# PWM_PPM_FMU_REV_1A.net
KiCad netlist of a schematic drawn in Altium Designer
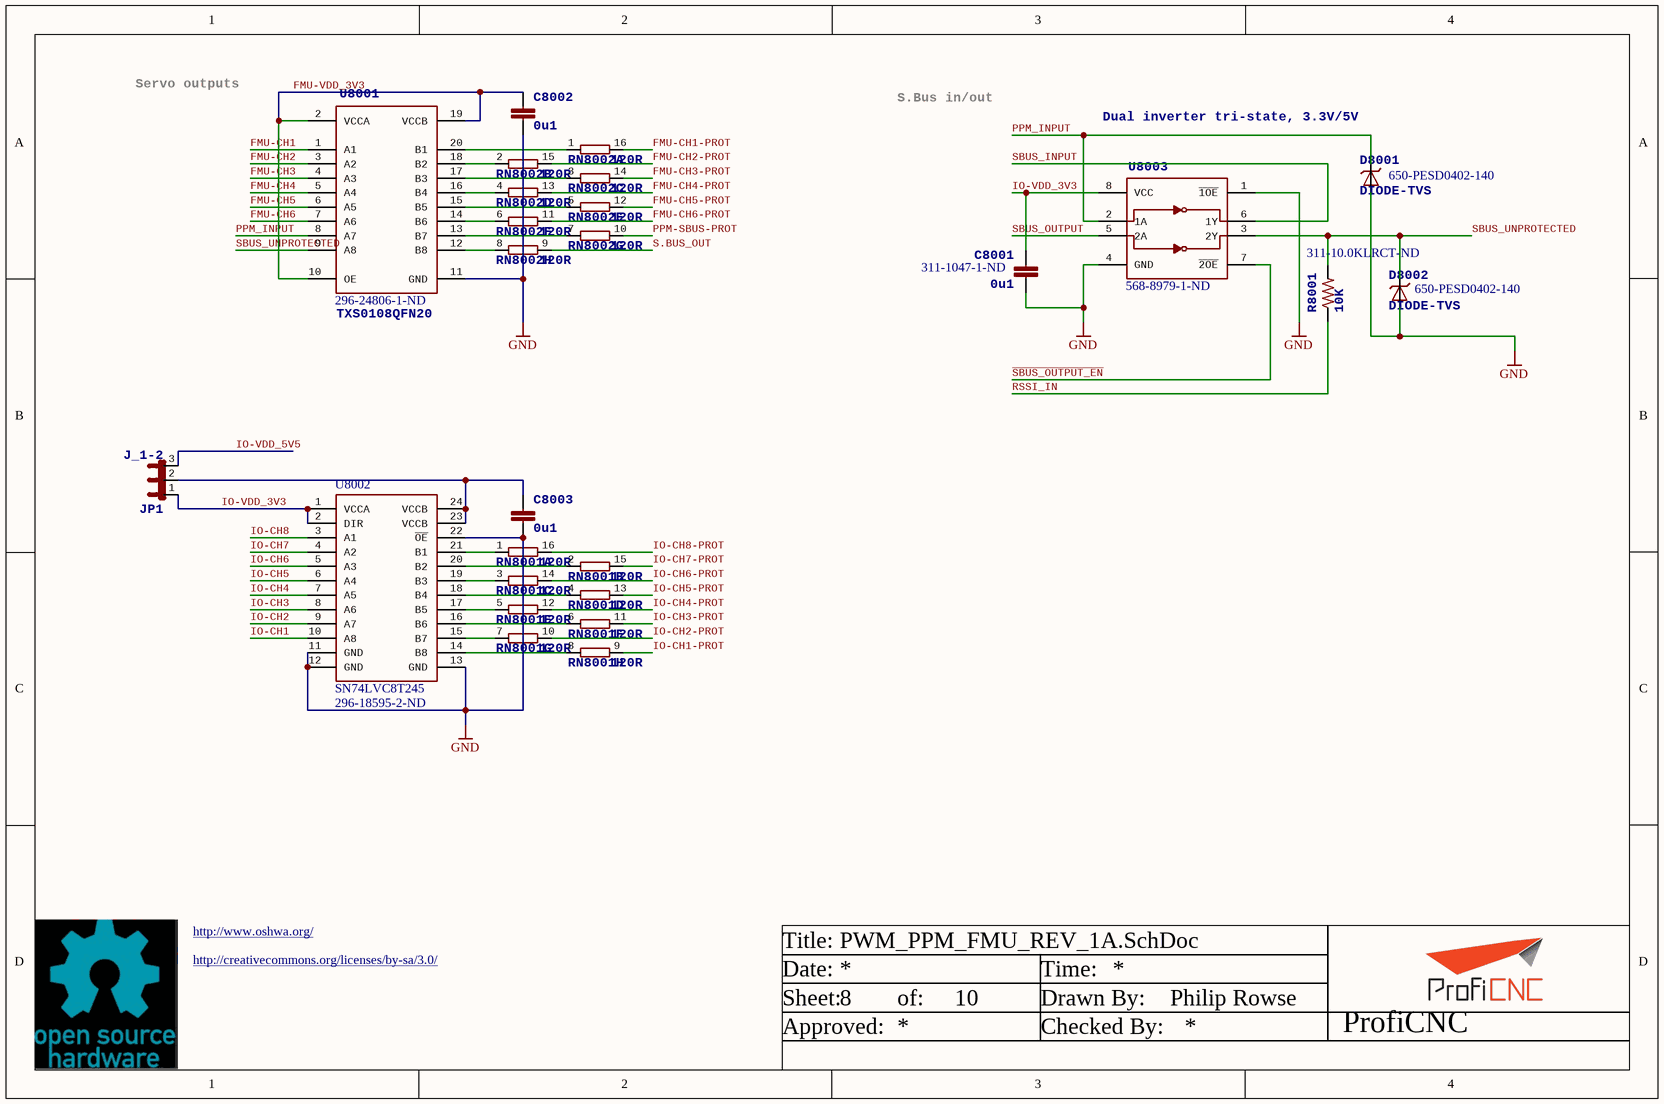
[diagram p0: PWM_PPM_FMU_REV_1A.SchDoc]

(export (version "E")
  (design (tool "Eeschema 10.0.6"))
  (components
    (comp (ref "C8001")
      (value "0u1")
      (footprint "0402-CAP")
      (description "CAP CER 0.1UF 16V Y5V 0402")
      (fields
        (field (name "PARTNO") "CC0402ZRY5V7BB104")
        (field (name "SUPPLIER PART NUMBER 1") "311-1047-1-ND")
        (field (name "3DR_PARTNO") "ECM0700")
      )
      (libsource (lib "") (part "CAP0402_1"))
    )
    (comp (ref "C8002")
      (value "0u1")
      (footprint "0402-CAP")
      (description "CAP CER 0.1UF 16V Y5V 0402")
      (fields (field (name "PARTNO") "CC0402ZRY5V7BB104") (field (name "3DR_PARTNO") "ECM0700"))
      (libsource (lib "pixhawk2") (part "CAP0402"))
    )
    (comp (ref "C8003")
      (value "0u1")
      (footprint "0402-CAP")
      (description "CAP CER 0.1UF 16V Y5V 0402")
      (fields (field (name "PARTNO") "CC0402ZRY5V7BB104") (field (name "3DR_PARTNO") "ECM0700"))
      (libsource (lib "pixhawk2") (part "CAP0402"))
    )
    (comp (ref "D8001")
      (value "DIODE-TVS")
      (footprint "0402-TVS")
      (description "TVS DIODE 14VWM 40VC 0402")
      (fields
        (field (name "SUPPLIER PART NUMBER 1") "650-PESD0402-140")
        (field (name "3DR_PARTNO") "ECM0837")
        (field (name "PARTNO") "PESD0402-140")
      )
      (libsource (lib "pixhawk2") (part "DIODE-TVS"))
    )
    (comp (ref "D8002")
      (value "DIODE-TVS")
      (footprint "0402-TVS")
      (description "TVS DIODE 14VWM 40VC 0402")
      (fields
        (field (name "SUPPLIER PART NUMBER 1") "650-PESD0402-140")
        (field (name "3DR_PARTNO") "ECM0837")
        (field (name "PARTNO") "PESD0402-140")
      )
      (libsource (lib "pixhawk2") (part "DIODE-TVS"))
    )
    (comp (ref "JP1")
      (value "J_1-2")
      (footprint "SJ_3_NO_PLACE_1-2_short")
      (libsource (lib "3DR") (part "JUMPER-31-2"))
    )
    (comp (ref "R8001")
      (value "10K")
      (footprint "0402-RES")
      (description "RES 10K OHM 1/16W 1% 0402 SMD")
      (fields
        (field (name "PARTNO") "RC0402FR-0710KL")
        (field (name "SUPPLIER PART NUMBER 1") "311-10.0KLRCT-ND")
        (field (name "3DR_PARTNO") "ECM0800")
      )
      (libsource (lib "pixhawk2") (part "RESISTOR0402-RES"))
    )
    (comp (ref "RN8001")
      (value "120R")
      (footprint "EXB2HV")
      (description "RES ARRAY 120 OHM 8 RES 1506")
      (fields (field (name "PARTNO") "EXB-2HV121JV") (field (name "3DR_PARTNO") "ECM0266"))
      (libsource (lib "pixhawk2") (part "8R-NEXB2HV-220R"))
    )
    (comp (ref "RN8002")
      (value "120R")
      (footprint "EXB2HV")
      (description "RES ARRAY 120 OHM 8 RES 1506")
      (fields (field (name "PARTNO") "EXB-2HV121JV") (field (name "3DR_PARTNO") "ECM0266"))
      (libsource (lib "pixhawk2") (part "8R-NEXB2HV-220R"))
    )
    (comp (ref "U8001")
      (value "TXS0108QFN20")
      (footprint "QFN20-RGY")
      (description "IC XLATR VOLT-LVL 8B BDIR 20QFN")
      (fields
        (field (name "SUPPLIER PART NUMBER 1") "296-24806-1-ND")
        (field (name "3DR_PARTNO") "ECM0845")
        (field (name "PARTNO") "TXS0108ERGYR")
      )
      (libsource (lib "pixhawk2") (part "TXS0108QFN20"))
    )
    (comp (ref "U8002")
      (value "SN74LVC8T245")
      (footprint "QFN24-RGY")
      (fields (field (name "SUPPLIER PART NUMBER 1") "296-18595-2-ND"))
      (libsource (lib "3DR") (part "SN74LVC8T245"))
    )
    (comp (ref "U8003")
      (value "Dual inverter tri-state, 3.3V/5V")
      (footprint "TSSOP8_SOT505-2")
      (description "IC INVERTER DUAL 4-INPUT 8TSSOP")
      (fields
        (field (name "SUPPLIER PART NUMBER 1") "568-8979-1-ND")
        (field (name "3DR_PARTNO") "ECM0817")
        (field (name "PARTNO") "74LVC2G240DP,125")
      )
      (libsource (lib "pixhawk2") (part "74LVC2G240-TSSOP-8"))
    )
  )
  (nets
    (net (code "1") (name "/FMU-CH1") (class "Default")
      (node (ref "U8001") (pin "1") (pinfunction "A1_1") (pintype "passive"))
    )
    (net (code "2") (name "/FMU-CH1-PROT") (class "Default")
      (node (ref "RN8002") (pin "16") (pinfunction "2_16") (pintype "passive"))
    )
    (net (code "3") (name "/FMU-CH2") (class "Default")
      (node (ref "U8001") (pin "3") (pinfunction "A2_3") (pintype "passive"))
    )
    (net (code "4") (name "/FMU-CH2-PROT") (class "Default")
      (node (ref "RN8002") (pin "15") (pinfunction "2_15") (pintype "passive"))
    )
    (net (code "5") (name "/FMU-CH3") (class "Default")
      (node (ref "U8001") (pin "4") (pinfunction "A3_4") (pintype "passive"))
    )
    (net (code "6") (name "/FMU-CH3-PROT") (class "Default")
      (node (ref "RN8002") (pin "14") (pinfunction "2_14") (pintype "passive"))
    )
    (net (code "7") (name "/FMU-CH4") (class "Default")
      (node (ref "U8001") (pin "5") (pinfunction "A4_5") (pintype "passive"))
    )
    (net (code "8") (name "/FMU-CH4-PROT") (class "Default")
      (node (ref "RN8002") (pin "13") (pinfunction "2_13") (pintype "passive"))
    )
    (net (code "9") (name "/FMU-CH5") (class "Default")
      (node (ref "U8001") (pin "6") (pinfunction "A5_6") (pintype "passive"))
    )
    (net (code "10") (name "/FMU-CH5-PROT") (class "Default")
      (node (ref "RN8002") (pin "12") (pinfunction "2_12") (pintype "passive"))
    )
    (net (code "11") (name "/FMU-CH6") (class "Default")
      (node (ref "U8001") (pin "7") (pinfunction "A6_7") (pintype "passive"))
    )
    (net (code "12") (name "/FMU-CH6-PROT") (class "Default")
      (node (ref "RN8002") (pin "11") (pinfunction "2_11") (pintype "passive"))
    )
    (net (code "13") (name "/FMU-VDD_3V3") (class "Default")
      (node (ref "C8002") (pin "P$1") (pinfunction "1_P$1") (pintype "passive"))
      (node (ref "U8001") (pin "10") (pinfunction "OE_10") (pintype "passive"))
      (node (ref "U8001") (pin "19") (pinfunction "VCCB_19") (pintype "passive"))
      (node (ref "U8001") (pin "2") (pinfunction "VCCA_2") (pintype "passive"))
    )
    (net (code "14") (name "/IO-CH1") (class "Default")
      (node (ref "U8002") (pin "10") (pinfunction "A8_10") (pintype "passive"))
    )
    (net (code "15") (name "/IO-CH1-PROT") (class "Default")
      (node (ref "RN8001") (pin "9") (pinfunction "2_9") (pintype "passive"))
    )
    (net (code "16") (name "/IO-CH2") (class "Default")
      (node (ref "U8002") (pin "9") (pinfunction "A7_9") (pintype "passive"))
    )
    (net (code "17") (name "/IO-CH2-PROT") (class "Default")
      (node (ref "RN8001") (pin "10") (pinfunction "2_10") (pintype "passive"))
    )
    (net (code "18") (name "/IO-CH3") (class "Default")
      (node (ref "U8002") (pin "8") (pinfunction "A6_8") (pintype "passive"))
    )
    (net (code "19") (name "/IO-CH3-PROT") (class "Default")
      (node (ref "RN8001") (pin "11") (pinfunction "2_11") (pintype "passive"))
    )
    (net (code "20") (name "/IO-CH4") (class "Default")
      (node (ref "U8002") (pin "7") (pinfunction "A5_7") (pintype "passive"))
    )
    (net (code "21") (name "/IO-CH4-PROT") (class "Default")
      (node (ref "RN8001") (pin "12") (pinfunction "2_12") (pintype "passive"))
    )
    (net (code "22") (name "/IO-CH5") (class "Default")
      (node (ref "U8002") (pin "6") (pinfunction "A4_6") (pintype "passive"))
    )
    (net (code "23") (name "/IO-CH5-PROT") (class "Default")
      (node (ref "RN8001") (pin "13") (pinfunction "2_13") (pintype "passive"))
    )
    (net (code "24") (name "/IO-CH6") (class "Default")
      (node (ref "U8002") (pin "5") (pinfunction "A3_5") (pintype "passive"))
    )
    (net (code "25") (name "/IO-CH6-PROT") (class "Default")
      (node (ref "RN8001") (pin "14") (pinfunction "2_14") (pintype "passive"))
    )
    (net (code "26") (name "/IO-CH7") (class "Default")
      (node (ref "U8002") (pin "4") (pinfunction "A2_4") (pintype "passive"))
    )
    (net (code "27") (name "/IO-CH7-PROT") (class "Default")
      (node (ref "RN8001") (pin "15") (pinfunction "2_15") (pintype "passive"))
    )
    (net (code "28") (name "/IO-CH8") (class "Default")
      (node (ref "U8002") (pin "3") (pinfunction "A1_3") (pintype "passive"))
    )
    (net (code "29") (name "/IO-CH8-PROT") (class "Default")
      (node (ref "RN8001") (pin "16") (pinfunction "2_16") (pintype "passive"))
    )
    (net (code "30") (name "/IO-VDD_3V3") (class "Default")
      (node (ref "C8001") (pin "P$1") (pinfunction "1_P$1") (pintype "passive"))
      (node (ref "JP1") (pin "1") (pinfunction "1_1") (pintype "passive"))
      (node (ref "U8002") (pin "1") (pinfunction "VCCA_1") (pintype "passive"))
      (node (ref "U8002") (pin "2") (pinfunction "DIR_2") (pintype "passive"))
      (node (ref "U8003") (pin "8") (pinfunction "VCC_8") (pintype "open_emitter"))
    )
    (net (code "31") (name "/IO-VDD_5V5") (class "Default")
      (node (ref "JP1") (pin "3") (pinfunction "3_3") (pintype "passive"))
    )
    (net (code "32") (name "/PPM-SBUS-PROT") (class "Default")
      (node (ref "RN8002") (pin "10") (pinfunction "2_10") (pintype "passive"))
    )
    (net (code "33") (name "/PPM_INPUT") (class "Default")
      (node (ref "D8001") (pin "C") (pinfunction "C_C") (pintype "passive"))
      (node (ref "U8001") (pin "8") (pinfunction "A7_8") (pintype "passive"))
      (node (ref "U8003") (pin "2") (pinfunction "1A_2") (pintype "passive"))
    )
    (net (code "34") (name "/RSSI_IN") (class "Default")
      (node (ref "R8001") (pin "P$1") (pinfunction "1_P$1") (pintype "passive"))
    )
    (net (code "35") (name "/S.BUS_OUT") (class "Default")
      (node (ref "RN8002") (pin "9") (pinfunction "2_9") (pintype "passive"))
    )
    (net (code "36") (name "/SBUS_INPUT") (class "Default")
      (node (ref "U8003") (pin "6") (pinfunction "1Y_6") (pintype "passive"))
    )
    (net (code "37") (name "/SBUS_OUTPUT") (class "Default")
      (node (ref "U8003") (pin "5") (pinfunction "2A_5") (pintype "passive"))
    )
    (net (code "38") (name "/SBUS_UNPROTECTED") (class "Default")
      (node (ref "D8002") (pin "C") (pinfunction "C_C") (pintype "passive"))
      (node (ref "R8001") (pin "P$2") (pinfunction "2_P$2") (pintype "passive"))
      (node (ref "U8001") (pin "9") (pinfunction "A8_9") (pintype "passive"))
      (node (ref "U8003") (pin "3") (pinfunction "2Y_3") (pintype "passive"))
    )
    (net (code "39") (name "/~{SBUS_OUTPUT_EN}") (class "Default")
      (node (ref "U8003") (pin "7") (pinfunction "~{2OE}_7") (pintype "passive"))
    )
    (net (code "40") (name "GND") (class "Default")
      (node (ref "C8001") (pin "P$2") (pinfunction "2_P$2") (pintype "passive"))
      (node (ref "C8002") (pin "P$2") (pinfunction "2_P$2") (pintype "passive"))
      (node (ref "C8003") (pin "P$2") (pinfunction "2_P$2") (pintype "passive"))
      (node (ref "D8001") (pin "A") (pinfunction "A_A") (pintype "passive"))
      (node (ref "D8002") (pin "A") (pinfunction "A_A") (pintype "passive"))
      (node (ref "U8001") (pin "11") (pinfunction "GND_11") (pintype "open_emitter"))
      (node (ref "U8002") (pin "11") (pinfunction "GND_11") (pintype "open_emitter"))
      (node (ref "U8002") (pin "12") (pinfunction "GND_12") (pintype "open_emitter"))
      (node (ref "U8002") (pin "13") (pinfunction "GND_13") (pintype "open_emitter"))
      (node (ref "U8002") (pin "22") (pinfunction "~{OE}_22") (pintype "passive"))
      (node (ref "U8003") (pin "1") (pinfunction "~{1OE}_1") (pintype "passive"))
      (node (ref "U8003") (pin "4") (pinfunction "GND_4") (pintype "open_emitter"))
    )
    (net (code "41") (name "Net-(C8003-1)") (class "Default")
      (node (ref "C8003") (pin "P$1") (pinfunction "1_P$1") (pintype "passive"))
      (node (ref "JP1") (pin "2") (pinfunction "2_2") (pintype "passive"))
      (node (ref "U8002") (pin "23") (pinfunction "VCCB_23") (pintype "passive"))
      (node (ref "U8002") (pin "24") (pinfunction "VCCB_24") (pintype "passive"))
    )
    (net (code "42") (name "Net-(RN8001B-1)") (class "Default")
      (node (ref "RN8001") (pin "2") (pinfunction "1_2") (pintype "passive"))
      (node (ref "U8002") (pin "20") (pinfunction "B2_20") (pintype "passive"))
    )
    (net (code "43") (name "Net-(RN8001C-1)") (class "Default")
      (node (ref "RN8001") (pin "3") (pinfunction "1_3") (pintype "passive"))
      (node (ref "U8002") (pin "19") (pinfunction "B3_19") (pintype "passive"))
    )
    (net (code "44") (name "Net-(RN8001D-1)") (class "Default")
      (node (ref "RN8001") (pin "4") (pinfunction "1_4") (pintype "passive"))
      (node (ref "U8002") (pin "18") (pinfunction "B4_18") (pintype "passive"))
    )
    (net (code "45") (name "Net-(RN8001E-1)") (class "Default")
      (node (ref "RN8001") (pin "5") (pinfunction "1_5") (pintype "passive"))
      (node (ref "U8002") (pin "17") (pinfunction "B5_17") (pintype "passive"))
    )
    (net (code "46") (name "Net-(RN8001F-1)") (class "Default")
      (node (ref "RN8001") (pin "6") (pinfunction "1_6") (pintype "passive"))
      (node (ref "U8002") (pin "16") (pinfunction "B6_16") (pintype "passive"))
    )
    (net (code "47") (name "Net-(RN8001G-1)") (class "Default")
      (node (ref "RN8001") (pin "7") (pinfunction "1_7") (pintype "passive"))
      (node (ref "U8002") (pin "15") (pinfunction "B7_15") (pintype "passive"))
    )
    (net (code "48") (name "Net-(RN8001H-1)") (class "Default")
      (node (ref "RN8001") (pin "8") (pinfunction "1_8") (pintype "passive"))
      (node (ref "U8002") (pin "14") (pinfunction "B8_14") (pintype "passive"))
    )
    (net (code "49") (name "Net-(RN8002B-1)") (class "Default")
      (node (ref "RN8002") (pin "2") (pinfunction "1_2") (pintype "passive"))
      (node (ref "U8001") (pin "18") (pinfunction "B2_18") (pintype "passive"))
    )
    (net (code "50") (name "Net-(RN8002C-1)") (class "Default")
      (node (ref "RN8002") (pin "3") (pinfunction "1_3") (pintype "passive"))
      (node (ref "U8001") (pin "17") (pinfunction "B3_17") (pintype "passive"))
    )
    (net (code "51") (name "Net-(RN8002D-1)") (class "Default")
      (node (ref "RN8002") (pin "4") (pinfunction "1_4") (pintype "passive"))
      (node (ref "U8001") (pin "16") (pinfunction "B4_16") (pintype "passive"))
    )
    (net (code "52") (name "Net-(RN8002E-1)") (class "Default")
      (node (ref "RN8002") (pin "5") (pinfunction "1_5") (pintype "passive"))
      (node (ref "U8001") (pin "15") (pinfunction "B5_15") (pintype "passive"))
    )
    (net (code "53") (name "Net-(RN8002F-1)") (class "Default")
      (node (ref "RN8002") (pin "6") (pinfunction "1_6") (pintype "passive"))
      (node (ref "U8001") (pin "14") (pinfunction "B6_14") (pintype "passive"))
    )
    (net (code "54") (name "Net-(RN8002G-1)") (class "Default")
      (node (ref "RN8002") (pin "7") (pinfunction "1_7") (pintype "passive"))
      (node (ref "U8001") (pin "13") (pinfunction "B7_13") (pintype "passive"))
    )
    (net (code "55") (name "Net-(RN8002H-1)") (class "Default")
      (node (ref "RN8002") (pin "8") (pinfunction "1_8") (pintype "passive"))
      (node (ref "U8001") (pin "12") (pinfunction "B8_12") (pintype "passive"))
    )
    (net (code "56") (name "Net-(U8001-B1)") (class "Default")
      (node (ref "RN8002") (pin "1") (pinfunction "1_1") (pintype "passive"))
      (node (ref "U8001") (pin "20") (pinfunction "B1_20") (pintype "passive"))
    )
    (net (code "57") (name "Net-(U8002-B1)") (class "Default")
      (node (ref "RN8001") (pin "1") (pinfunction "1_1") (pintype "passive"))
      (node (ref "U8002") (pin "21") (pinfunction "B1_21") (pintype "passive"))
    )
  )
)
